# pmu.net
KiCad netlist of a schematic drawn in EAGLE
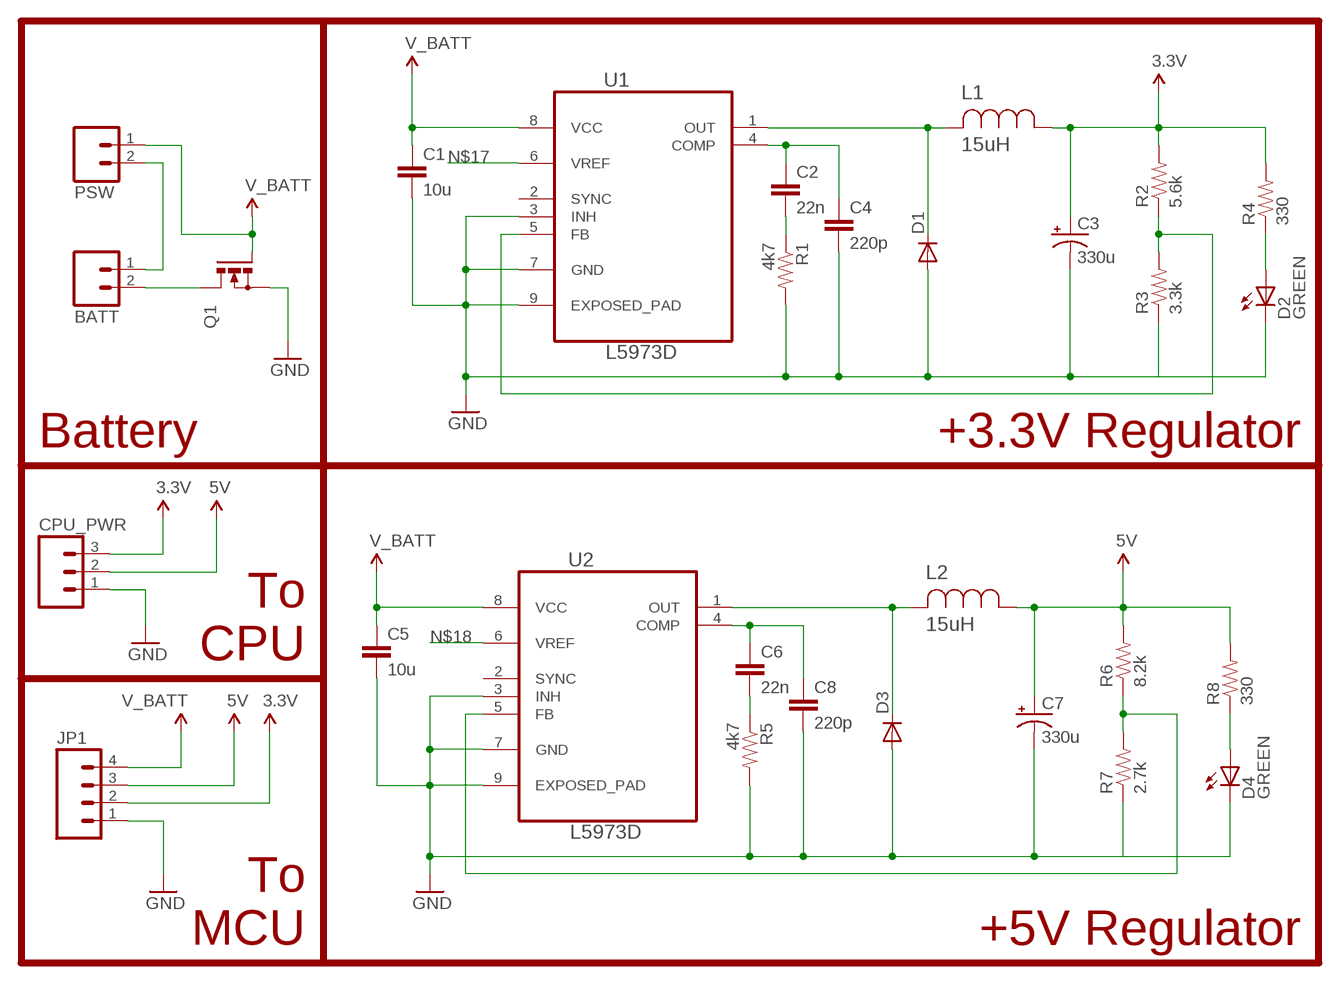
[diagram p0: schematic, sheet 1]

(export (version "E")
  (design (tool "Eeschema 10.0.6"))
  (components
    (comp (ref "BATT")
      (value "M02PTH")
      (footprint "eagle-import:1X02")
      (libsource (lib "eagle-import") (part "M02PTH"))
    )
    (comp (ref "C1")
      (value "10u")
      (footprint "eagle-import:1210")
      (libsource (lib "eagle-import") (part "CAP1210"))
    )
    (comp (ref "C2")
      (value "22n")
      (footprint "eagle-import:0805")
      (libsource (lib "eagle-import") (part "CAP0805"))
    )
    (comp (ref "C3")
      (value "330u")
      (footprint "eagle-import:EIA7343")
      (libsource (lib "eagle-import") (part "CAP_POL7343"))
    )
    (comp (ref "C4")
      (value "220p")
      (footprint "eagle-import:0805")
      (libsource (lib "eagle-import") (part "CAP0805"))
    )
    (comp (ref "C5")
      (value "10u")
      (footprint "eagle-import:1210")
      (libsource (lib "eagle-import") (part "CAP1210"))
    )
    (comp (ref "C6")
      (value "22n")
      (footprint "eagle-import:0805")
      (libsource (lib "eagle-import") (part "CAP0805"))
    )
    (comp (ref "C7")
      (value "330u")
      (footprint "eagle-import:EIA7343")
      (libsource (lib "eagle-import") (part "CAP_POL7343"))
    )
    (comp (ref "C8")
      (value "220p")
      (footprint "eagle-import:0805")
      (libsource (lib "eagle-import") (part "CAP0805"))
    )
    (comp (ref "CPU_PWR")
      (value "M03PTH")
      (footprint "eagle-import:1X03")
      (libsource (lib "eagle-import") (part "M03PTH"))
    )
    (comp (ref "D1")
      (value "DIODESMB")
      (footprint "eagle-import:SMB-DIODE")
      (libsource (lib "eagle-import") (part "DIODESMB"))
    )
    (comp (ref "D2")
      (value "GREEN")
      (footprint "eagle-import:CHIP-LED0805")
      (libsource (lib "eagle-import") (part "LEDCHIP-LED0805"))
    )
    (comp (ref "D3")
      (value "DIODESMB")
      (footprint "eagle-import:SMB-DIODE")
      (libsource (lib "eagle-import") (part "DIODESMB"))
    )
    (comp (ref "D4")
      (value "GREEN")
      (footprint "eagle-import:CHIP-LED0805")
      (libsource (lib "eagle-import") (part "LEDCHIP-LED0805"))
    )
    (comp (ref "JP1")
      (value "M04PTH")
      (footprint "eagle-import:1X04")
      (libsource (lib "eagle-import") (part "M04PTH"))
    )
    (comp (ref "L1")
      (value "15uH")
      (footprint "eagle-import:IND_ELL8TP")
      (fields (field (name "MPN") "ELL8TP150MB"))
      (libsource (lib "eagle-import") (part "ELL-8TP8TP150MB"))
    )
    (comp (ref "L2")
      (value "15uH")
      (footprint "eagle-import:IND_ELL8TP")
      (fields (field (name "MPN") "ELL8TP150MB"))
      (libsource (lib "eagle-import") (part "ELL-8TP8TP150MB"))
    )
    (comp (ref "PSW")
      (value "M02PTH")
      (footprint "eagle-import:1X02")
      (libsource (lib "eagle-import") (part "M02PTH"))
    )
    (comp (ref "Q1")
      (value "N-MOSFET-SO8S")
      (footprint "eagle-import:SO-08")
      (libsource (lib "eagle-import") (part "N-MOSFET-SO8S"))
    )
    (comp (ref "R1")
      (value "4k7")
      (footprint "eagle-import:0805")
      (libsource (lib "eagle-import") (part "RESISTOR0805-RES"))
    )
    (comp (ref "R2")
      (value "5.6k")
      (footprint "eagle-import:0805")
      (libsource (lib "eagle-import") (part "RESISTOR0805-RES"))
    )
    (comp (ref "R3")
      (value "3.3k")
      (footprint "eagle-import:0805")
      (libsource (lib "eagle-import") (part "RESISTOR0805-RES"))
    )
    (comp (ref "R4")
      (value "330")
      (footprint "eagle-import:0805")
      (libsource (lib "eagle-import") (part "RESISTOR0805-RES"))
    )
    (comp (ref "R5")
      (value "4k7")
      (footprint "eagle-import:0805")
      (libsource (lib "eagle-import") (part "RESISTOR0805-RES"))
    )
    (comp (ref "R6")
      (value "8.2k")
      (footprint "eagle-import:0805")
      (libsource (lib "eagle-import") (part "RESISTOR0805-RES"))
    )
    (comp (ref "R7")
      (value "2.7k")
      (footprint "eagle-import:0805")
      (libsource (lib "eagle-import") (part "RESISTOR0805-RES"))
    )
    (comp (ref "R8")
      (value "330")
      (footprint "eagle-import:0805")
      (libsource (lib "eagle-import") (part "RESISTOR0805-RES"))
    )
    (comp (ref "U1")
      (value "L5973D")
      (footprint "eagle-import:SOP127P600X170-9N")
      (libsource (lib "eagle-import") (part "L5973D"))
    )
    (comp (ref "U2")
      (value "L5973D")
      (footprint "eagle-import:SOP127P600X170-9N")
      (libsource (lib "eagle-import") (part "L5973D"))
    )
  )
  (nets
    (net (code "1") (name "/N$17") (class "Default")
      (node (ref "U1") (pin "6") (pinfunction "VREF_6") (pintype "power_in"))
    )
    (net (code "2") (name "/N$18") (class "Default")
      (node (ref "U2") (pin "6") (pinfunction "VREF_6") (pintype "power_in"))
    )
    (net (code "3") (name "3.3V") (class "Default")
      (node (ref "C3") (pin "A") (pinfunction "+_A") (pintype "passive"))
      (node (ref "CPU_PWR") (pin "3") (pinfunction "3_3") (pintype "passive"))
      (node (ref "JP1") (pin "2") (pinfunction "2_2") (pintype "passive"))
      (node (ref "L1") (pin "1") (pinfunction "1_1") (pintype "passive"))
      (node (ref "R2") (pin "2") (pinfunction "2_2") (pintype "passive"))
      (node (ref "R4") (pin "2") (pinfunction "2_2") (pintype "passive"))
    )
    (net (code "4") (name "5V") (class "Default")
      (node (ref "C7") (pin "A") (pinfunction "+_A") (pintype "passive"))
      (node (ref "CPU_PWR") (pin "2") (pinfunction "2_2") (pintype "passive"))
      (node (ref "JP1") (pin "3") (pinfunction "3_3") (pintype "passive"))
      (node (ref "L2") (pin "1") (pinfunction "1_1") (pintype "passive"))
      (node (ref "R6") (pin "2") (pinfunction "2_2") (pintype "passive"))
      (node (ref "R8") (pin "2") (pinfunction "2_2") (pintype "passive"))
    )
    (net (code "5") (name "GND") (class "Default")
      (node (ref "C1") (pin "2") (pinfunction "2_2") (pintype "passive"))
      (node (ref "C3") (pin "C") (pinfunction "-_C") (pintype "passive"))
      (node (ref "C4") (pin "2") (pinfunction "2_2") (pintype "passive"))
      (node (ref "C5") (pin "2") (pinfunction "2_2") (pintype "passive"))
      (node (ref "C7") (pin "C") (pinfunction "-_C") (pintype "passive"))
      (node (ref "C8") (pin "2") (pinfunction "2_2") (pintype "passive"))
      (node (ref "CPU_PWR") (pin "1") (pinfunction "1_1") (pintype "passive"))
      (node (ref "D1") (pin "A") (pinfunction "A_A") (pintype "passive"))
      (node (ref "D2") (pin "C") (pinfunction "C_C") (pintype "passive"))
      (node (ref "D3") (pin "A") (pinfunction "A_A") (pintype "passive"))
      (node (ref "D4") (pin "C") (pinfunction "C_C") (pintype "passive"))
      (node (ref "JP1") (pin "1") (pinfunction "1_1") (pintype "passive"))
      (node (ref "Q1") (pin "1") (pinfunction "S_1") (pintype "passive"))
      (node (ref "Q1") (pin "2") (pinfunction "S_2") (pintype "passive"))
      (node (ref "Q1") (pin "3") (pinfunction "S_3") (pintype "passive"))
      (node (ref "R1") (pin "2") (pinfunction "2_2") (pintype "passive"))
      (node (ref "R3") (pin "1") (pinfunction "1_1") (pintype "passive"))
      (node (ref "R5") (pin "2") (pinfunction "2_2") (pintype "passive"))
      (node (ref "R7") (pin "1") (pinfunction "1_1") (pintype "passive"))
      (node (ref "U1") (pin "3") (pinfunction "INH_3") (pintype "input"))
      (node (ref "U1") (pin "7") (pinfunction "GND_7") (pintype "passive"))
      (node (ref "U1") (pin "9") (pinfunction "EXPOSED_PAD_9") (pintype "passive"))
      (node (ref "U2") (pin "3") (pinfunction "INH_3") (pintype "input"))
      (node (ref "U2") (pin "7") (pinfunction "GND_7") (pintype "passive"))
      (node (ref "U2") (pin "9") (pinfunction "EXPOSED_PAD_9") (pintype "passive"))
    )
    (net (code "6") (name "Net-(BATT-Pad1)") (class "Default")
      (node (ref "BATT") (pin "1") (pinfunction "1_1") (pintype "passive"))
      (node (ref "PSW") (pin "2") (pinfunction "2_2") (pintype "passive"))
    )
    (net (code "7") (name "Net-(BATT-Pad2)") (class "Default")
      (node (ref "BATT") (pin "2") (pinfunction "2_2") (pintype "passive"))
      (node (ref "Q1") (pin "5") (pinfunction "D_5") (pintype "passive"))
      (node (ref "Q1") (pin "6") (pinfunction "D_6") (pintype "passive"))
      (node (ref "Q1") (pin "7") (pinfunction "D_7") (pintype "passive"))
      (node (ref "Q1") (pin "8") (pinfunction "D_8") (pintype "passive"))
    )
    (net (code "8") (name "Net-(C2-Pad2)") (class "Default")
      (node (ref "C2") (pin "2") (pinfunction "2_2") (pintype "passive"))
      (node (ref "R1") (pin "1") (pinfunction "1_1") (pintype "passive"))
    )
    (net (code "9") (name "Net-(C6-Pad2)") (class "Default")
      (node (ref "C6") (pin "2") (pinfunction "2_2") (pintype "passive"))
      (node (ref "R5") (pin "1") (pinfunction "1_1") (pintype "passive"))
    )
    (net (code "10") (name "Net-(D2-PadA)") (class "Default")
      (node (ref "D2") (pin "A") (pinfunction "A_A") (pintype "passive"))
      (node (ref "R4") (pin "1") (pinfunction "1_1") (pintype "passive"))
    )
    (net (code "11") (name "Net-(D4-PadA)") (class "Default")
      (node (ref "D4") (pin "A") (pinfunction "A_A") (pintype "passive"))
      (node (ref "R8") (pin "1") (pinfunction "1_1") (pintype "passive"))
    )
    (net (code "12") (name "Net-(U1-COMP)") (class "Default")
      (node (ref "C2") (pin "1") (pinfunction "1_1") (pintype "passive"))
      (node (ref "C4") (pin "1") (pinfunction "1_1") (pintype "passive"))
      (node (ref "U1") (pin "4") (pinfunction "COMP_4") (pintype "output"))
    )
    (net (code "13") (name "Net-(U1-FB)") (class "Default")
      (node (ref "R2") (pin "1") (pinfunction "1_1") (pintype "passive"))
      (node (ref "R3") (pin "2") (pinfunction "2_2") (pintype "passive"))
      (node (ref "U1") (pin "5") (pinfunction "FB_5") (pintype "input"))
    )
    (net (code "14") (name "Net-(U1-OUT)") (class "Default")
      (node (ref "D1") (pin "C") (pinfunction "C_C") (pintype "passive"))
      (node (ref "L1") (pin "2") (pinfunction "2_2") (pintype "passive"))
      (node (ref "U1") (pin "1") (pinfunction "OUT_1") (pintype "output"))
    )
    (net (code "15") (name "Net-(U2-COMP)") (class "Default")
      (node (ref "C6") (pin "1") (pinfunction "1_1") (pintype "passive"))
      (node (ref "C8") (pin "1") (pinfunction "1_1") (pintype "passive"))
      (node (ref "U2") (pin "4") (pinfunction "COMP_4") (pintype "output"))
    )
    (net (code "16") (name "Net-(U2-FB)") (class "Default")
      (node (ref "R6") (pin "1") (pinfunction "1_1") (pintype "passive"))
      (node (ref "R7") (pin "2") (pinfunction "2_2") (pintype "passive"))
      (node (ref "U2") (pin "5") (pinfunction "FB_5") (pintype "input"))
    )
    (net (code "17") (name "Net-(U2-OUT)") (class "Default")
      (node (ref "D3") (pin "C") (pinfunction "C_C") (pintype "passive"))
      (node (ref "L2") (pin "2") (pinfunction "2_2") (pintype "passive"))
      (node (ref "U2") (pin "1") (pinfunction "OUT_1") (pintype "output"))
    )
    (net (code "18") (name "V_BATT") (class "Default")
      (node (ref "C1") (pin "1") (pinfunction "1_1") (pintype "passive"))
      (node (ref "C5") (pin "1") (pinfunction "1_1") (pintype "passive"))
      (node (ref "JP1") (pin "4") (pinfunction "4_4") (pintype "passive"))
      (node (ref "PSW") (pin "1") (pinfunction "1_1") (pintype "passive"))
      (node (ref "Q1") (pin "4") (pinfunction "G_4") (pintype "passive"))
      (node (ref "U1") (pin "8") (pinfunction "VCC_8") (pintype "power_in"))
      (node (ref "U2") (pin "8") (pinfunction "VCC_8") (pintype "power_in"))
    )
    (net (code "19") (name "unconnected-(U1-SYNC-Pad2)") (class "Default")
      (node (ref "U1") (pin "2") (pinfunction "SYNC_2") (pintype "input"))
    )
    (net (code "20") (name "unconnected-(U2-SYNC-Pad2)") (class "Default")
      (node (ref "U2") (pin "2") (pinfunction "SYNC_2") (pintype "input"))
    )
  )
)
